# SCH_axp173_3a3036_2022-11-21.net
KiCad netlist of a schematic drawn in EasyEDA
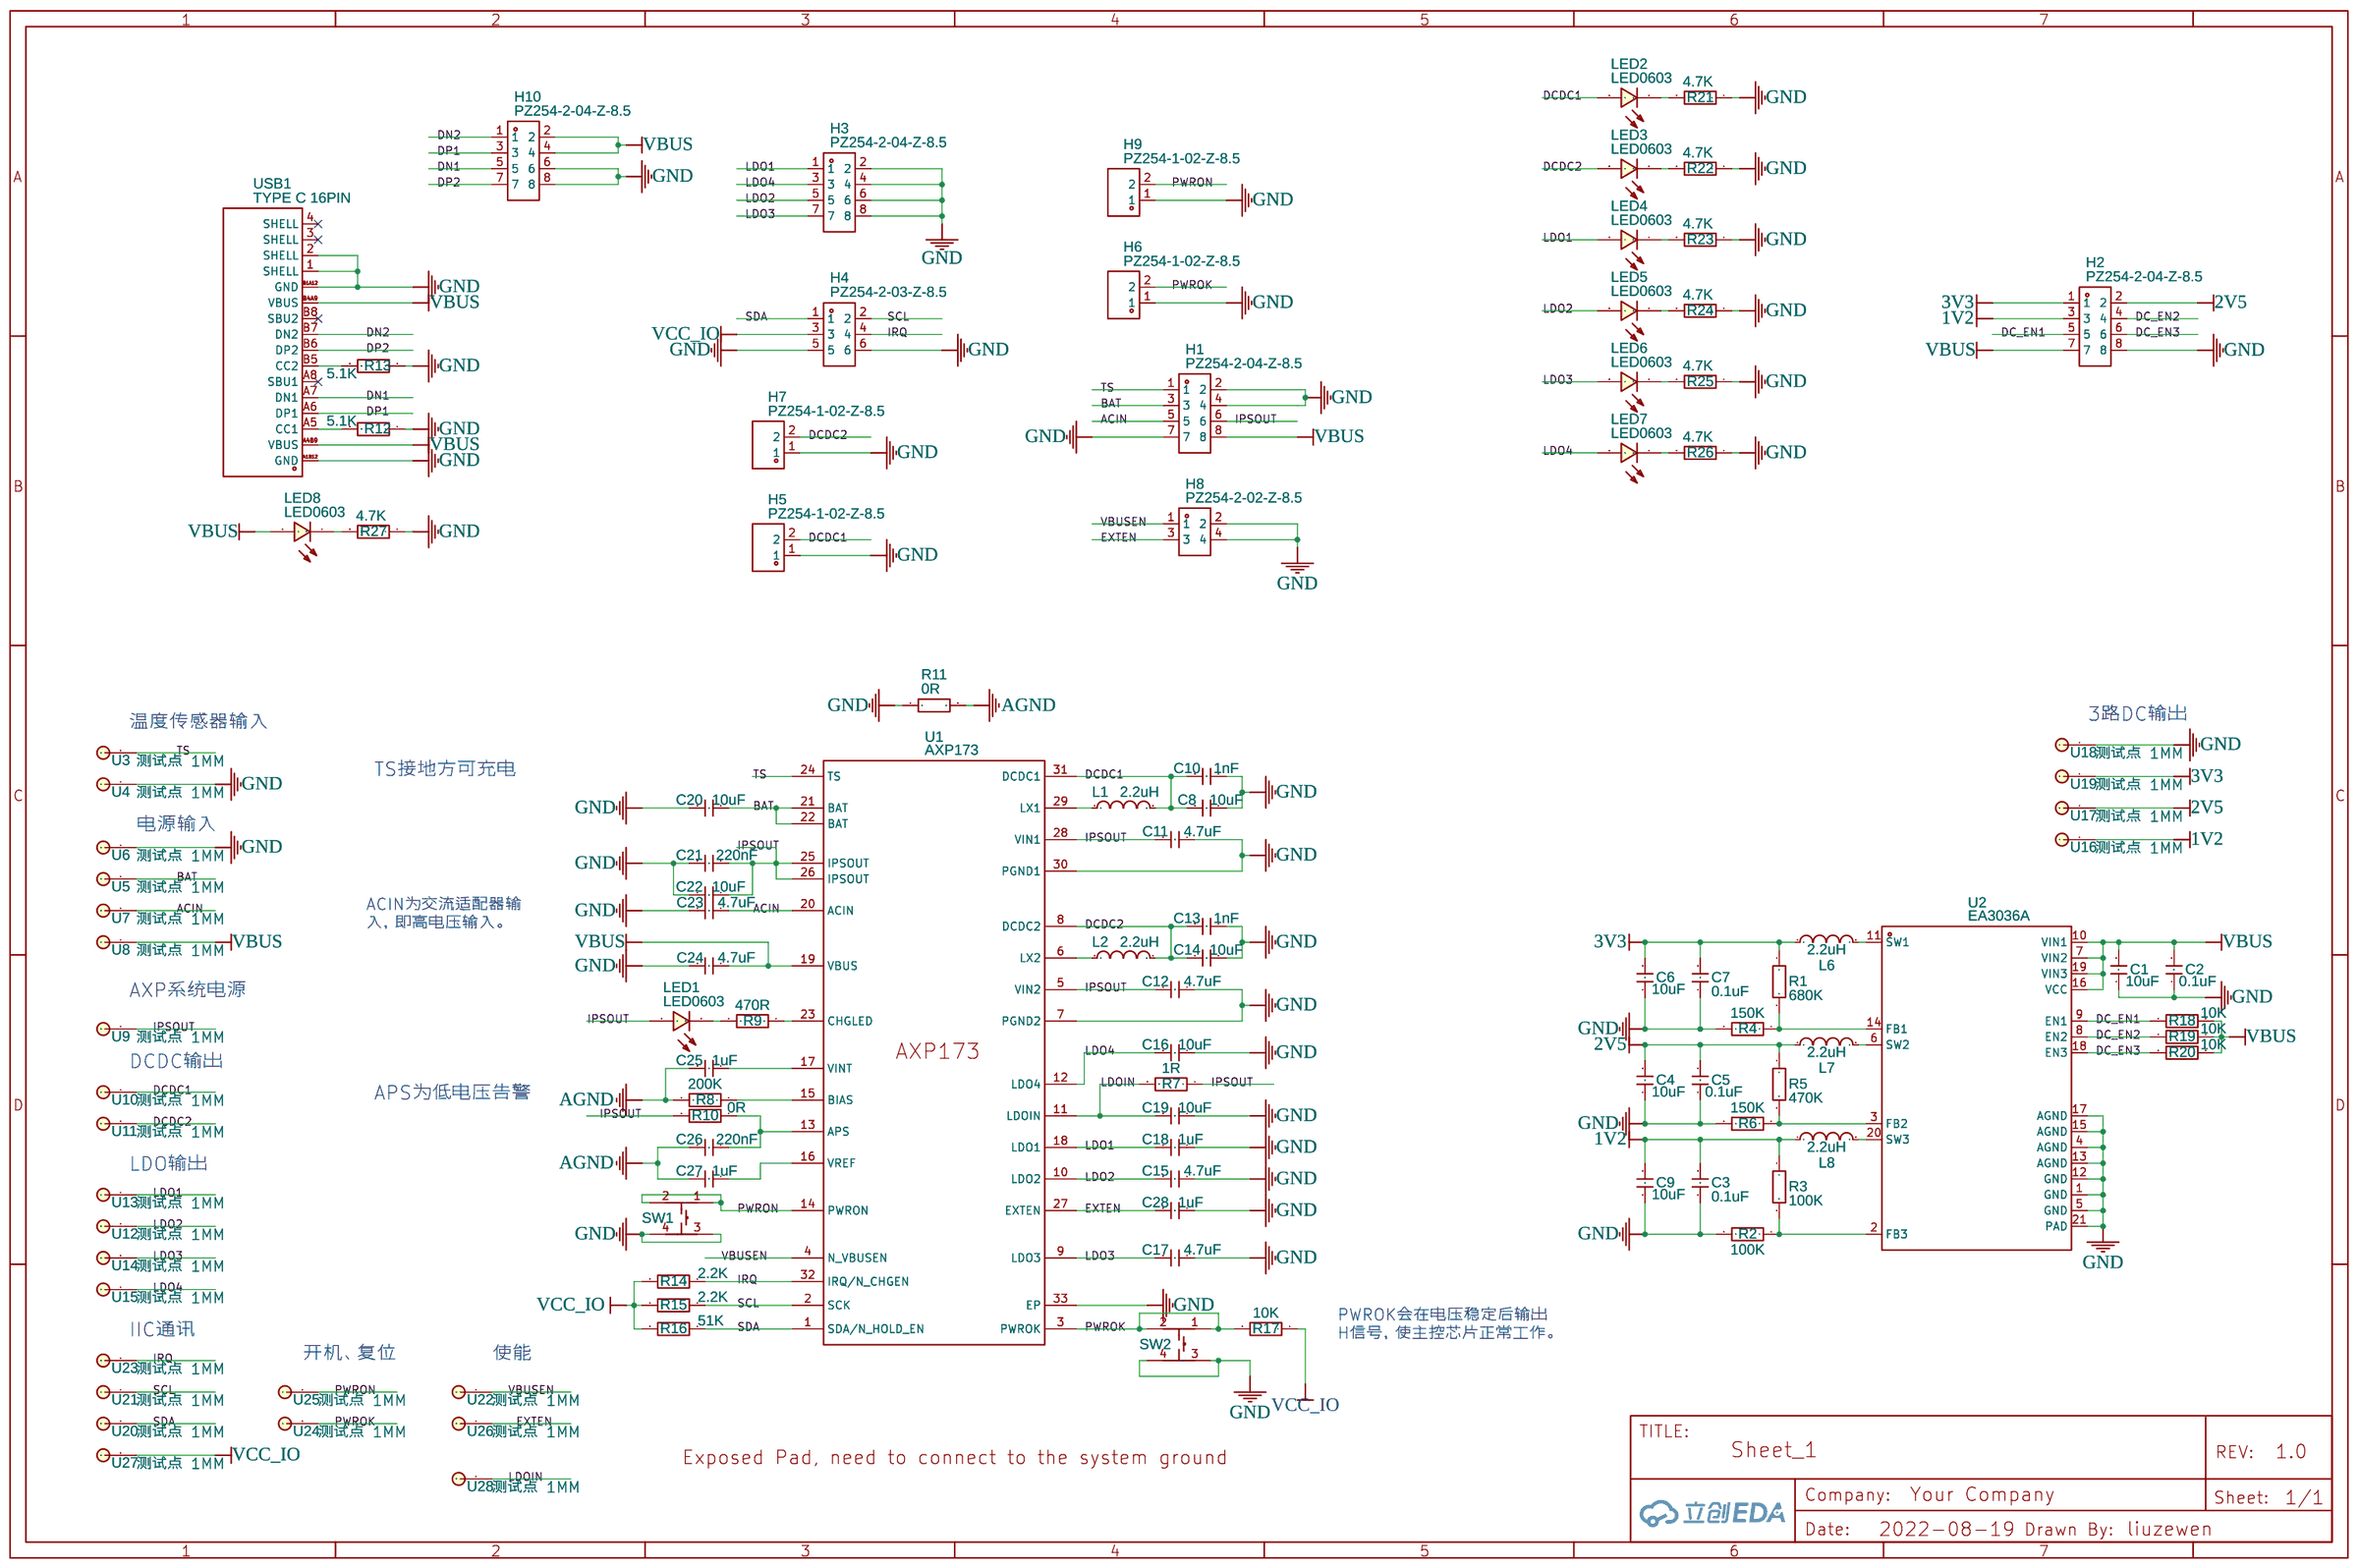
[diagram p0: schematic sheet]

(export (version "E")
  (design (tool "Eeschema 10.0.6"))
  (components
    (comp (ref "C1") (value "10uF") (libsource (lib "") (part "C0603_1")))
    (comp (ref "C2") (value "0.1uF") (libsource (lib "") (part "C0603_1")))
    (comp (ref "C3") (value "0.1uF") (libsource (lib "") (part "C0603_1")))
    (comp (ref "C4") (value "10uF") (libsource (lib "") (part "C0603_1")))
    (comp (ref "C5") (value "0.1uF") (libsource (lib "") (part "C0603_1")))
    (comp (ref "C6") (value "10uF") (libsource (lib "") (part "C0603_1")))
    (comp (ref "C7") (value "0.1uF") (libsource (lib "") (part "C0603_1")))
    (comp (ref "C8") (value "10uF") (libsource (lib "") (part "C0603")))
    (comp (ref "C9") (value "10uF") (libsource (lib "") (part "C0603_1")))
    (comp (ref "C10") (value "1nF") (libsource (lib "") (part "C0603")))
    (comp (ref "C11") (value "4.7uF") (libsource (lib "") (part "C0603")))
    (comp (ref "C12") (value "4.7uF") (libsource (lib "") (part "C0603")))
    (comp (ref "C13") (value "1nF") (libsource (lib "") (part "C0603")))
    (comp (ref "C14") (value "10uF") (libsource (lib "") (part "C0603")))
    (comp (ref "C15") (value "4.7uF") (libsource (lib "") (part "C0603")))
    (comp (ref "C16") (value "10uF") (libsource (lib "") (part "C0603")))
    (comp (ref "C17") (value "4.7uF") (libsource (lib "") (part "C0603")))
    (comp (ref "C18") (value "1uF") (libsource (lib "") (part "C0603")))
    (comp (ref "C19") (value "10uF") (libsource (lib "") (part "C0603")))
    (comp (ref "C20") (value "10uF") (libsource (lib "") (part "C0603")))
    (comp (ref "C21") (value "220nF") (libsource (lib "") (part "C0603")))
    (comp (ref "C22") (value "10uF") (libsource (lib "") (part "C0603")))
    (comp (ref "C23") (value "4.7uF") (libsource (lib "") (part "C0603")))
    (comp (ref "C24") (value "4.7uF") (libsource (lib "") (part "C0603")))
    (comp (ref "C25") (value "1uF") (libsource (lib "") (part "C0603")))
    (comp (ref "C26") (value "220nF") (libsource (lib "") (part "C0603")))
    (comp (ref "C27") (value "1uF") (libsource (lib "") (part "C0603")))
    (comp (ref "C28") (value "1uF") (libsource (lib "") (part "C0603")))
    (comp (ref "H1")
      (value "PZ254-2-04-Z-8.5")
      (fields (field (name "BOM_Supplier Part") "C2894965"))
      (libsource (lib "") (part "PZ254-2-04-Z-8.5"))
    )
    (comp (ref "H2")
      (value "PZ254-2-04-Z-8.5")
      (fields (field (name "BOM_Supplier Part") "C2894965"))
      (libsource (lib "") (part "PZ254-2-04-Z-8.5"))
    )
    (comp (ref "H3")
      (value "PZ254-2-04-Z-8.5")
      (fields (field (name "BOM_Supplier Part") "C2894965"))
      (libsource (lib "") (part "PZ254-2-04-Z-8.5"))
    )
    (comp (ref "H4")
      (value "PZ254-2-03-Z-8.5")
      (fields (field (name "BOM_Supplier Part") "C2894964"))
      (libsource (lib "") (part "PZ254-2-03-Z-8.5"))
    )
    (comp (ref "H5")
      (value "PZ254-1-02-Z-8.5")
      (fields (field (name "BOM_Supplier Part") "C2894925"))
      (libsource (lib "") (part "PZ254-1-02-Z-8.5"))
    )
    (comp (ref "H6")
      (value "PZ254-1-02-Z-8.5")
      (fields (field (name "BOM_Supplier Part") "C2894925"))
      (libsource (lib "") (part "PZ254-1-02-Z-8.5"))
    )
    (comp (ref "H7")
      (value "PZ254-1-02-Z-8.5")
      (fields (field (name "BOM_Supplier Part") "C2894925"))
      (libsource (lib "") (part "PZ254-1-02-Z-8.5"))
    )
    (comp (ref "H8")
      (value "PZ254-2-02-Z-8.5")
      (fields (field (name "BOM_Supplier Part") "C2894963"))
      (libsource (lib "") (part "PZ254-2-02-Z-8.5"))
    )
    (comp (ref "H9")
      (value "PZ254-1-02-Z-8.5")
      (fields (field (name "BOM_Supplier Part") "C2894925"))
      (libsource (lib "") (part "PZ254-1-02-Z-8.5"))
    )
    (comp (ref "H10")
      (value "PZ254-2-04-Z-8.5")
      (fields (field (name "BOM_Supplier Part") "C2894965"))
      (libsource (lib "") (part "PZ254-2-04-Z-8.5"))
    )
    (comp (ref "L1")
      (value "2.2uH")
      (fields
        (field (name "BOM_Manufacturer Part") "FNR252010S2R2NT")
        (field (name "BOM_Supplier Part") "C167682")
      )
      (libsource (lib "") (part "FNR252010S2R2NT"))
    )
    (comp (ref "L2")
      (value "2.2uH")
      (fields
        (field (name "BOM_Manufacturer Part") "FNR252010S2R2NT")
        (field (name "BOM_Supplier Part") "C167682")
      )
      (libsource (lib "") (part "FNR252010S2R2NT"))
    )
    (comp (ref "L6")
      (value "2.2uH")
      (fields
        (field (name "BOM_Manufacturer Part") "CKCS201610-2.2uH/M-N")
        (field (name "BOM_Supplier Part") "C354533")
      )
      (libsource (lib "") (part "CKCS201610-2.2UH/M-N"))
    )
    (comp (ref "L7")
      (value "2.2uH")
      (fields
        (field (name "BOM_Manufacturer Part") "CKCS201610-2.2uH/M-N")
        (field (name "BOM_Supplier Part") "C354533")
      )
      (libsource (lib "") (part "CKCS201610-2.2UH/M-N"))
    )
    (comp (ref "L8")
      (value "2.2uH")
      (fields
        (field (name "BOM_Manufacturer Part") "CKCS201610-2.2uH/M-N")
        (field (name "BOM_Supplier Part") "C354533")
      )
      (libsource (lib "") (part "CKCS201610-2.2UH/M-N"))
    )
    (comp (ref "LED1") (value "LED0603") (libsource (lib "") (part "LED0603")))
    (comp (ref "LED2") (value "LED0603") (libsource (lib "") (part "LED0603")))
    (comp (ref "LED3") (value "LED0603") (libsource (lib "") (part "LED0603")))
    (comp (ref "LED4") (value "LED0603") (libsource (lib "") (part "LED0603")))
    (comp (ref "LED5") (value "LED0603") (libsource (lib "") (part "LED0603")))
    (comp (ref "LED6") (value "LED0603") (libsource (lib "") (part "LED0603")))
    (comp (ref "LED7") (value "LED0603") (libsource (lib "") (part "LED0603")))
    (comp (ref "LED8") (value "LED0603") (libsource (lib "") (part "LED0603")))
    (comp (ref "R1") (value "680K") (libsource (lib "") (part "R0603")))
    (comp (ref "R2") (value "100K") (libsource (lib "") (part "R0603_1")))
    (comp (ref "R3") (value "100K") (libsource (lib "") (part "R0603")))
    (comp (ref "R4") (value "150K") (libsource (lib "") (part "R0603_1")))
    (comp (ref "R5") (value "470K") (libsource (lib "") (part "R0603")))
    (comp (ref "R6") (value "150K") (libsource (lib "") (part "R0603_1")))
    (comp (ref "R7") (value "1R") (libsource (lib "") (part "R0603_1")))
    (comp (ref "R8") (value "200K") (libsource (lib "") (part "R0603_1")))
    (comp (ref "R9") (value "470R") (libsource (lib "") (part "R0603_1")))
    (comp (ref "R10") (value "0R") (libsource (lib "") (part "R0603_1")))
    (comp (ref "R11") (value "0R") (libsource (lib "") (part "R0603_2")))
    (comp (ref "R12") (value "5.1K") (libsource (lib "") (part "R0603_1")))
    (comp (ref "R13") (value "5.1K") (libsource (lib "") (part "R0603_1")))
    (comp (ref "R14") (value "2.2K") (libsource (lib "") (part "R0603_1")))
    (comp (ref "R15") (value "2.2K") (libsource (lib "") (part "R0603_1")))
    (comp (ref "R16") (value "51K") (libsource (lib "") (part "R0603_1")))
    (comp (ref "R17") (value "10K") (libsource (lib "") (part "R0603_1")))
    (comp (ref "R18") (value "10K") (libsource (lib "") (part "R0603_1")))
    (comp (ref "R19") (value "10K") (libsource (lib "") (part "R0603_1")))
    (comp (ref "R20") (value "10K") (libsource (lib "") (part "R0603_1")))
    (comp (ref "R21") (value "4.7K") (libsource (lib "") (part "R0603_1")))
    (comp (ref "R22") (value "4.7K") (libsource (lib "") (part "R0603_1")))
    (comp (ref "R23") (value "4.7K") (libsource (lib "") (part "R0603_1")))
    (comp (ref "R24") (value "4.7K") (libsource (lib "") (part "R0603_1")))
    (comp (ref "R25") (value "4.7K") (libsource (lib "") (part "R0603_1")))
    (comp (ref "R26") (value "4.7K") (libsource (lib "") (part "R0603_1")))
    (comp (ref "R27") (value "4.7K") (libsource (lib "") (part "R0603_1")))
    (comp (ref "SW1")
      (value "UK-B0267-SP25Y")
      (fields (field (name "BOM_Supplier Part") "C493283"))
      (libsource (lib "") (part "UK-B0267-SP25Y"))
    )
    (comp (ref "SW2")
      (value "UK-B0267-SP25Y")
      (fields (field (name "BOM_Supplier Part") "C493283"))
      (libsource (lib "") (part "UK-B0267-SP25Y"))
    )
    (comp (ref "U1")
      (value "AXP173")
      (fields (field (name "BOM_Manufacturer Part") "AXP209"))
      (libsource (lib "") (part "AXP173"))
    )
    (comp (ref "U2") (value "EA3036A") (libsource (lib "") (part "EA3036A")))
    (comp (ref "U3") (value "测试点 1MM") (libsource (lib "") (part "测试点 1MM")))
    (comp (ref "U4") (value "测试点 1MM") (libsource (lib "") (part "测试点 1MM")))
    (comp (ref "U5") (value "测试点 1MM") (libsource (lib "") (part "测试点 1MM")))
    (comp (ref "U6") (value "测试点 1MM") (libsource (lib "") (part "测试点 1MM")))
    (comp (ref "U7") (value "测试点 1MM") (libsource (lib "") (part "测试点 1MM")))
    (comp (ref "U8") (value "测试点 1MM") (libsource (lib "") (part "测试点 1MM")))
    (comp (ref "U9") (value "测试点 1MM") (libsource (lib "") (part "测试点 1MM")))
    (comp (ref "U10") (value "测试点 1MM") (libsource (lib "") (part "测试点 1MM")))
    (comp (ref "U11") (value "测试点 1MM") (libsource (lib "") (part "测试点 1MM")))
    (comp (ref "U12") (value "测试点 1MM") (libsource (lib "") (part "测试点 1MM")))
    (comp (ref "U13") (value "测试点 1MM") (libsource (lib "") (part "测试点 1MM")))
    (comp (ref "U14") (value "测试点 1MM") (libsource (lib "") (part "测试点 1MM")))
    (comp (ref "U15") (value "测试点 1MM") (libsource (lib "") (part "测试点 1MM")))
    (comp (ref "U16") (value "测试点 1MM") (libsource (lib "") (part "测试点 1MM")))
    (comp (ref "U17") (value "测试点 1MM") (libsource (lib "") (part "测试点 1MM")))
    (comp (ref "U18") (value "测试点 1MM") (libsource (lib "") (part "测试点 1MM")))
    (comp (ref "U19") (value "测试点 1MM") (libsource (lib "") (part "测试点 1MM")))
    (comp (ref "U20") (value "测试点 1MM") (libsource (lib "") (part "测试点 1MM")))
    (comp (ref "U21") (value "测试点 1MM") (libsource (lib "") (part "测试点 1MM")))
    (comp (ref "U22") (value "测试点 1MM") (libsource (lib "") (part "测试点 1MM")))
    (comp (ref "U23") (value "测试点 1MM") (libsource (lib "") (part "测试点 1MM")))
    (comp (ref "U24") (value "测试点 1MM") (libsource (lib "") (part "测试点 1MM")))
    (comp (ref "U25") (value "测试点 1MM") (libsource (lib "") (part "测试点 1MM")))
    (comp (ref "U26") (value "测试点 1MM") (libsource (lib "") (part "测试点 1MM")))
    (comp (ref "U27") (value "测试点 1MM") (libsource (lib "") (part "测试点 1MM")))
    (comp (ref "U28") (value "测试点 1MM") (libsource (lib "") (part "测试点 1MM")))
    (comp (ref "USB1")
      (value "TYPE C 16PIN")
      (fields
        (field (name "BOM_Manufacturer Part") "TYPE-C16PIN")
        (field (name "BOM_Supplier Part") "C393939")
      )
      (libsource (lib "") (part "TYPE C 16PIN"))
    )
  )
  (nets
    (net (code "1") (name "/ACIN") (class "Default")
      (node (ref "C23") (pin "1") (pinfunction "1_1") (pintype "unspecified"))
      (node (ref "H1") (pin "5") (pinfunction "5_5") (pintype "unspecified"))
      (node (ref "U1") (pin "20") (pinfunction "ACIN_20") (pintype "unspecified"))
      (node (ref "U7") (pin "1") (pinfunction "1_1") (pintype "unspecified"))
    )
    (net (code "2") (name "/BAT") (class "Default")
      (node (ref "C20") (pin "1") (pinfunction "1_1") (pintype "unspecified"))
      (node (ref "H1") (pin "3") (pinfunction "3_3") (pintype "unspecified"))
      (node (ref "U1") (pin "21") (pinfunction "BAT_21") (pintype "unspecified"))
      (node (ref "U1") (pin "22") (pinfunction "BAT_22") (pintype "unspecified"))
      (node (ref "U5") (pin "1") (pinfunction "1_1") (pintype "unspecified"))
    )
    (net (code "3") (name "/DCDC1") (class "Default")
      (node (ref "C10") (pin "2") (pinfunction "2_2") (pintype "unspecified"))
      (node (ref "C8") (pin "2") (pinfunction "2_2") (pintype "unspecified"))
      (node (ref "H5") (pin "2") (pinfunction "2_2") (pintype "unspecified"))
      (node (ref "L1") (pin "2") (pinfunction "2_2") (pintype "unspecified"))
      (node (ref "LED2") (pin "2") (pinfunction "A_2") (pintype "input"))
      (node (ref "U1") (pin "31") (pinfunction "DCDC1_31") (pintype "unspecified"))
      (node (ref "U10") (pin "1") (pinfunction "1_1") (pintype "unspecified"))
    )
    (net (code "4") (name "/DCDC2") (class "Default")
      (node (ref "C13") (pin "2") (pinfunction "2_2") (pintype "unspecified"))
      (node (ref "C14") (pin "2") (pinfunction "2_2") (pintype "unspecified"))
      (node (ref "H7") (pin "2") (pinfunction "2_2") (pintype "unspecified"))
      (node (ref "L2") (pin "2") (pinfunction "2_2") (pintype "unspecified"))
      (node (ref "LED3") (pin "2") (pinfunction "A_2") (pintype "input"))
      (node (ref "U1") (pin "8") (pinfunction "DCDC2_8") (pintype "unspecified"))
      (node (ref "U11") (pin "1") (pinfunction "1_1") (pintype "unspecified"))
    )
    (net (code "5") (name "/DC_EN1") (class "Default")
      (node (ref "H2") (pin "5") (pinfunction "5_5") (pintype "unspecified"))
      (node (ref "R18") (pin "2") (pinfunction "2_2") (pintype "input"))
      (node (ref "U2") (pin "9") (pinfunction "EN1_9") (pintype "unspecified"))
    )
    (net (code "6") (name "/DC_EN2") (class "Default")
      (node (ref "H2") (pin "4") (pinfunction "4_4") (pintype "unspecified"))
      (node (ref "R19") (pin "2") (pinfunction "2_2") (pintype "input"))
      (node (ref "U2") (pin "8") (pinfunction "EN2_8") (pintype "unspecified"))
    )
    (net (code "7") (name "/DC_EN3") (class "Default")
      (node (ref "H2") (pin "6") (pinfunction "6_6") (pintype "unspecified"))
      (node (ref "R20") (pin "2") (pinfunction "2_2") (pintype "input"))
      (node (ref "U2") (pin "18") (pinfunction "EN3_18") (pintype "unspecified"))
    )
    (net (code "8") (name "/DN1") (class "Default")
      (node (ref "H10") (pin "5") (pinfunction "5_5") (pintype "unspecified"))
      (node (ref "USB1") (pin "A7") (pinfunction "DN1_A7") (pintype "unspecified"))
    )
    (net (code "9") (name "/DN2") (class "Default")
      (node (ref "H10") (pin "1") (pinfunction "1_1") (pintype "unspecified"))
      (node (ref "USB1") (pin "B7") (pinfunction "DN2_B7") (pintype "unspecified"))
    )
    (net (code "10") (name "/DP1") (class "Default")
      (node (ref "H10") (pin "3") (pinfunction "3_3") (pintype "unspecified"))
      (node (ref "USB1") (pin "A6") (pinfunction "DP1_A6") (pintype "unspecified"))
    )
    (net (code "11") (name "/DP2") (class "Default")
      (node (ref "H10") (pin "7") (pinfunction "7_7") (pintype "unspecified"))
      (node (ref "USB1") (pin "B6") (pinfunction "DP2_B6") (pintype "unspecified"))
    )
    (net (code "12") (name "/EXTEN") (class "Default")
      (node (ref "C28") (pin "2") (pinfunction "2_2") (pintype "unspecified"))
      (node (ref "H8") (pin "3") (pinfunction "3_3") (pintype "unspecified"))
      (node (ref "U1") (pin "27") (pinfunction "EXTEN_27") (pintype "unspecified"))
      (node (ref "U26") (pin "1") (pinfunction "1_1") (pintype "unspecified"))
    )
    (net (code "13") (name "/IPSOUT") (class "Default")
      (node (ref "C11") (pin "2") (pinfunction "2_2") (pintype "unspecified"))
      (node (ref "C12") (pin "2") (pinfunction "2_2") (pintype "unspecified"))
      (node (ref "C21") (pin "1") (pinfunction "1_1") (pintype "unspecified"))
      (node (ref "C22") (pin "1") (pinfunction "1_1") (pintype "unspecified"))
      (node (ref "H1") (pin "6") (pinfunction "6_6") (pintype "unspecified"))
      (node (ref "LED1") (pin "2") (pinfunction "A_2") (pintype "input"))
      (node (ref "R10") (pin "2") (pinfunction "2_2") (pintype "input"))
      (node (ref "R7") (pin "1") (pinfunction "1_1") (pintype "input"))
      (node (ref "U1") (pin "25") (pinfunction "IPSOUT_25") (pintype "unspecified"))
      (node (ref "U1") (pin "26") (pinfunction "IPSOUT_26") (pintype "unspecified"))
      (node (ref "U1") (pin "28") (pinfunction "VIN1_28") (pintype "unspecified"))
      (node (ref "U1") (pin "5") (pinfunction "VIN2_5") (pintype "unspecified"))
      (node (ref "U9") (pin "1") (pinfunction "1_1") (pintype "unspecified"))
    )
    (net (code "14") (name "/IRQ") (class "Default")
      (node (ref "H4") (pin "4") (pinfunction "4_4") (pintype "unspecified"))
      (node (ref "R14") (pin "1") (pinfunction "1_1") (pintype "input"))
      (node (ref "U1") (pin "32") (pinfunction "IRQ/N_CHGEN_32") (pintype "unspecified"))
      (node (ref "U23") (pin "1") (pinfunction "1_1") (pintype "unspecified"))
    )
    (net (code "15") (name "/LDO1") (class "Default")
      (node (ref "C18") (pin "2") (pinfunction "2_2") (pintype "unspecified"))
      (node (ref "H3") (pin "1") (pinfunction "1_1") (pintype "unspecified"))
      (node (ref "LED4") (pin "2") (pinfunction "A_2") (pintype "input"))
      (node (ref "U1") (pin "18") (pinfunction "LDO1_18") (pintype "unspecified"))
      (node (ref "U13") (pin "1") (pinfunction "1_1") (pintype "unspecified"))
    )
    (net (code "16") (name "/LDO2") (class "Default")
      (node (ref "C15") (pin "2") (pinfunction "2_2") (pintype "unspecified"))
      (node (ref "H3") (pin "5") (pinfunction "5_5") (pintype "unspecified"))
      (node (ref "LED5") (pin "2") (pinfunction "A_2") (pintype "input"))
      (node (ref "U1") (pin "10") (pinfunction "LDO2_10") (pintype "unspecified"))
      (node (ref "U12") (pin "1") (pinfunction "1_1") (pintype "unspecified"))
    )
    (net (code "17") (name "/LDO3") (class "Default")
      (node (ref "C17") (pin "2") (pinfunction "2_2") (pintype "unspecified"))
      (node (ref "H3") (pin "7") (pinfunction "7_7") (pintype "unspecified"))
      (node (ref "LED6") (pin "2") (pinfunction "A_2") (pintype "input"))
      (node (ref "U1") (pin "9") (pinfunction "LDO3_9") (pintype "unspecified"))
      (node (ref "U14") (pin "1") (pinfunction "1_1") (pintype "unspecified"))
    )
    (net (code "18") (name "/LDO4") (class "Default")
      (node (ref "C16") (pin "2") (pinfunction "2_2") (pintype "unspecified"))
      (node (ref "H3") (pin "3") (pinfunction "3_3") (pintype "unspecified"))
      (node (ref "LED7") (pin "2") (pinfunction "A_2") (pintype "input"))
      (node (ref "U1") (pin "12") (pinfunction "LDO4_12") (pintype "unspecified"))
      (node (ref "U15") (pin "1") (pinfunction "1_1") (pintype "unspecified"))
    )
    (net (code "19") (name "/LDOIN") (class "Default")
      (node (ref "C19") (pin "2") (pinfunction "2_2") (pintype "unspecified"))
      (node (ref "R7") (pin "2") (pinfunction "2_2") (pintype "input"))
      (node (ref "U1") (pin "11") (pinfunction "LDOIN_11") (pintype "unspecified"))
      (node (ref "U28") (pin "1") (pinfunction "1_1") (pintype "unspecified"))
    )
    (net (code "20") (name "/PWROK") (class "Default")
      (node (ref "H6") (pin "2") (pinfunction "2_2") (pintype "unspecified"))
      (node (ref "R17") (pin "2") (pinfunction "2_2") (pintype "input"))
      (node (ref "SW2") (pin "1") (pinfunction "1_1") (pintype "unspecified"))
      (node (ref "SW2") (pin "2") (pinfunction "2_2") (pintype "unspecified"))
      (node (ref "U1") (pin "3") (pinfunction "PWROK_3") (pintype "unspecified"))
      (node (ref "U24") (pin "1") (pinfunction "1_1") (pintype "unspecified"))
    )
    (net (code "21") (name "/PWRON") (class "Default")
      (node (ref "H9") (pin "2") (pinfunction "2_2") (pintype "unspecified"))
      (node (ref "SW1") (pin "1") (pinfunction "1_1") (pintype "unspecified"))
      (node (ref "SW1") (pin "2") (pinfunction "2_2") (pintype "unspecified"))
      (node (ref "U1") (pin "14") (pinfunction "PWRON_14") (pintype "unspecified"))
      (node (ref "U25") (pin "1") (pinfunction "1_1") (pintype "unspecified"))
    )
    (net (code "22") (name "/SCL") (class "Default")
      (node (ref "H4") (pin "2") (pinfunction "2_2") (pintype "unspecified"))
      (node (ref "R15") (pin "1") (pinfunction "1_1") (pintype "input"))
      (node (ref "U1") (pin "2") (pinfunction "SCK_2") (pintype "unspecified"))
      (node (ref "U21") (pin "1") (pinfunction "1_1") (pintype "unspecified"))
    )
    (net (code "23") (name "/SDA") (class "Default")
      (node (ref "H4") (pin "1") (pinfunction "1_1") (pintype "unspecified"))
      (node (ref "R16") (pin "1") (pinfunction "1_1") (pintype "input"))
      (node (ref "U1") (pin "1") (pinfunction "SDA/N_HOLD_EN_1") (pintype "unspecified"))
      (node (ref "U20") (pin "1") (pinfunction "1_1") (pintype "unspecified"))
    )
    (net (code "24") (name "/TS") (class "Default")
      (node (ref "H1") (pin "1") (pinfunction "1_1") (pintype "unspecified"))
      (node (ref "U1") (pin "24") (pinfunction "TS_24") (pintype "unspecified"))
      (node (ref "U3") (pin "1") (pinfunction "1_1") (pintype "unspecified"))
    )
    (net (code "25") (name "/VBUSEN") (class "Default")
      (node (ref "H8") (pin "1") (pinfunction "1_1") (pintype "unspecified"))
      (node (ref "U1") (pin "4") (pinfunction "N_VBUSEN_4") (pintype "unspecified"))
      (node (ref "U22") (pin "1") (pinfunction "1_1") (pintype "unspecified"))
    )
    (net (code "26") (name "1V2") (class "Default")
      (node (ref "C3") (pin "2") (pinfunction "2_2") (pintype "unspecified"))
      (node (ref "C9") (pin "2") (pinfunction "2_2") (pintype "unspecified"))
      (node (ref "H2") (pin "3") (pinfunction "3_3") (pintype "unspecified"))
      (node (ref "L8") (pin "1") (pinfunction "1_1") (pintype "unspecified"))
      (node (ref "R3") (pin "1") (pinfunction "1_1") (pintype "input"))
      (node (ref "U16") (pin "1") (pinfunction "1_1") (pintype "unspecified"))
    )
    (net (code "27") (name "2V5") (class "Default")
      (node (ref "C4") (pin "2") (pinfunction "2_2") (pintype "unspecified"))
      (node (ref "C5") (pin "2") (pinfunction "2_2") (pintype "unspecified"))
      (node (ref "H2") (pin "2") (pinfunction "2_2") (pintype "unspecified"))
      (node (ref "L7") (pin "1") (pinfunction "1_1") (pintype "unspecified"))
      (node (ref "R5") (pin "1") (pinfunction "1_1") (pintype "input"))
      (node (ref "U17") (pin "1") (pinfunction "1_1") (pintype "unspecified"))
    )
    (net (code "28") (name "3V3") (class "Default")
      (node (ref "C6") (pin "2") (pinfunction "2_2") (pintype "unspecified"))
      (node (ref "C7") (pin "2") (pinfunction "2_2") (pintype "unspecified"))
      (node (ref "H2") (pin "1") (pinfunction "1_1") (pintype "unspecified"))
      (node (ref "L6") (pin "1") (pinfunction "1_1") (pintype "unspecified"))
      (node (ref "R1") (pin "1") (pinfunction "1_1") (pintype "input"))
      (node (ref "U19") (pin "1") (pinfunction "1_1") (pintype "unspecified"))
    )
    (net (code "29") (name "AGND") (class "Default")
      (node (ref "C25") (pin "2") (pinfunction "2_2") (pintype "unspecified"))
      (node (ref "C26") (pin "2") (pinfunction "2_2") (pintype "unspecified"))
      (node (ref "C27") (pin "2") (pinfunction "2_2") (pintype "unspecified"))
      (node (ref "R11") (pin "2") (pinfunction "2_2") (pintype "input"))
      (node (ref "R8") (pin "2") (pinfunction "2_2") (pintype "input"))
    )
    (net (code "30") (name "GND") (class "Default")
      (node (ref "C1") (pin "1") (pinfunction "1_1") (pintype "unspecified"))
      (node (ref "C10") (pin "1") (pinfunction "1_1") (pintype "unspecified"))
      (node (ref "C11") (pin "1") (pinfunction "1_1") (pintype "unspecified"))
      (node (ref "C12") (pin "1") (pinfunction "1_1") (pintype "unspecified"))
      (node (ref "C13") (pin "1") (pinfunction "1_1") (pintype "unspecified"))
      (node (ref "C14") (pin "1") (pinfunction "1_1") (pintype "unspecified"))
      (node (ref "C15") (pin "1") (pinfunction "1_1") (pintype "unspecified"))
      (node (ref "C16") (pin "1") (pinfunction "1_1") (pintype "unspecified"))
      (node (ref "C17") (pin "1") (pinfunction "1_1") (pintype "unspecified"))
      (node (ref "C18") (pin "1") (pinfunction "1_1") (pintype "unspecified"))
      (node (ref "C19") (pin "1") (pinfunction "1_1") (pintype "unspecified"))
      (node (ref "C2") (pin "1") (pinfunction "1_1") (pintype "unspecified"))
      (node (ref "C20") (pin "2") (pinfunction "2_2") (pintype "unspecified"))
      (node (ref "C21") (pin "2") (pinfunction "2_2") (pintype "unspecified"))
      (node (ref "C22") (pin "2") (pinfunction "2_2") (pintype "unspecified"))
      (node (ref "C23") (pin "2") (pinfunction "2_2") (pintype "unspecified"))
      (node (ref "C24") (pin "2") (pinfunction "2_2") (pintype "unspecified"))
      (node (ref "C28") (pin "1") (pinfunction "1_1") (pintype "unspecified"))
      (node (ref "C3") (pin "1") (pinfunction "1_1") (pintype "unspecified"))
      (node (ref "C4") (pin "1") (pinfunction "1_1") (pintype "unspecified"))
      (node (ref "C5") (pin "1") (pinfunction "1_1") (pintype "unspecified"))
      (node (ref "C6") (pin "1") (pinfunction "1_1") (pintype "unspecified"))
      (node (ref "C7") (pin "1") (pinfunction "1_1") (pintype "unspecified"))
      (node (ref "C8") (pin "1") (pinfunction "1_1") (pintype "unspecified"))
      (node (ref "C9") (pin "1") (pinfunction "1_1") (pintype "unspecified"))
      (node (ref "H1") (pin "2") (pinfunction "2_2") (pintype "unspecified"))
      (node (ref "H1") (pin "4") (pinfunction "4_4") (pintype "unspecified"))
      (node (ref "H1") (pin "7") (pinfunction "7_7") (pintype "unspecified"))
      (node (ref "H10") (pin "6") (pinfunction "6_6") (pintype "unspecified"))
      (node (ref "H10") (pin "8") (pinfunction "8_8") (pintype "unspecified"))
      (node (ref "H2") (pin "8") (pinfunction "8_8") (pintype "unspecified"))
      (node (ref "H3") (pin "2") (pinfunction "2_2") (pintype "unspecified"))
      (node (ref "H3") (pin "4") (pinfunction "4_4") (pintype "unspecified"))
      (node (ref "H3") (pin "6") (pinfunction "6_6") (pintype "unspecified"))
      (node (ref "H3") (pin "8") (pinfunction "8_8") (pintype "unspecified"))
      (node (ref "H4") (pin "5") (pinfunction "5_5") (pintype "unspecified"))
      (node (ref "H4") (pin "6") (pinfunction "6_6") (pintype "unspecified"))
      (node (ref "H5") (pin "1") (pinfunction "1_1") (pintype "unspecified"))
      (node (ref "H6") (pin "1") (pinfunction "1_1") (pintype "unspecified"))
      (node (ref "H7") (pin "1") (pinfunction "1_1") (pintype "unspecified"))
      (node (ref "H8") (pin "2") (pinfunction "2_2") (pintype "unspecified"))
      (node (ref "H8") (pin "4") (pinfunction "4_4") (pintype "unspecified"))
      (node (ref "H9") (pin "1") (pinfunction "1_1") (pintype "unspecified"))
      (node (ref "R11") (pin "1") (pinfunction "1_1") (pintype "input"))
      (node (ref "R12") (pin "1") (pinfunction "1_1") (pintype "input"))
      (node (ref "R13") (pin "1") (pinfunction "1_1") (pintype "input"))
      (node (ref "R2") (pin "2") (pinfunction "2_2") (pintype "input"))
      (node (ref "R21") (pin "1") (pinfunction "1_1") (pintype "input"))
      (node (ref "R22") (pin "1") (pinfunction "1_1") (pintype "input"))
      (node (ref "R23") (pin "1") (pinfunction "1_1") (pintype "input"))
      (node (ref "R24") (pin "1") (pinfunction "1_1") (pintype "input"))
      (node (ref "R25") (pin "1") (pinfunction "1_1") (pintype "input"))
      (node (ref "R26") (pin "1") (pinfunction "1_1") (pintype "input"))
      (node (ref "R27") (pin "1") (pinfunction "1_1") (pintype "input"))
      (node (ref "R4") (pin "2") (pinfunction "2_2") (pintype "input"))
      (node (ref "R6") (pin "2") (pinfunction "2_2") (pintype "input"))
      (node (ref "SW1") (pin "3") (pinfunction "3_3") (pintype "unspecified"))
      (node (ref "SW1") (pin "4") (pinfunction "4_4") (pintype "unspecified"))
      (node (ref "SW2") (pin "3") (pinfunction "3_3") (pintype "unspecified"))
      (node (ref "SW2") (pin "4") (pinfunction "4_4") (pintype "unspecified"))
      (node (ref "U1") (pin "30") (pinfunction "PGND1_30") (pintype "unspecified"))
      (node (ref "U1") (pin "33") (pinfunction "EP_33") (pintype "unspecified"))
      (node (ref "U1") (pin "7") (pinfunction "PGND2_7") (pintype "unspecified"))
      (node (ref "U18") (pin "1") (pinfunction "1_1") (pintype "unspecified"))
      (node (ref "U2") (pin "1") (pinfunction "GND_1") (pintype "unspecified"))
      (node (ref "U2") (pin "12") (pinfunction "GND_12") (pintype "unspecified"))
      (node (ref "U2") (pin "13") (pinfunction "AGND_13") (pintype "unspecified"))
      (node (ref "U2") (pin "15") (pinfunction "AGND_15") (pintype "unspecified"))
      (node (ref "U2") (pin "17") (pinfunction "AGND_17") (pintype "unspecified"))
      (node (ref "U2") (pin "21") (pinfunction "PAD_21") (pintype "unspecified"))
      (node (ref "U2") (pin "4") (pinfunction "AGND_4") (pintype "unspecified"))
      (node (ref "U2") (pin "5") (pinfunction "GND_5") (pintype "unspecified"))
      (node (ref "U4") (pin "1") (pinfunction "1_1") (pintype "unspecified"))
      (node (ref "U6") (pin "1") (pinfunction "1_1") (pintype "unspecified"))
      (node (ref "USB1") (pin "1") (pinfunction "SHELL_1") (pintype "unspecified"))
      (node (ref "USB1") (pin "2") (pinfunction "SHELL_2") (pintype "unspecified"))
      (node (ref "USB1") (pin "A1B12") (pinfunction "GND_A1B12") (pintype "unspecified"))
      (node (ref "USB1") (pin "B1A12") (pinfunction "GND_B1A12") (pintype "unspecified"))
    )
    (net (code "31") (name "Net-(LED1-C)") (class "Default")
      (node (ref "LED1") (pin "1") (pinfunction "C_1") (pintype "input"))
      (node (ref "R9") (pin "2") (pinfunction "2_2") (pintype "input"))
    )
    (net (code "32") (name "Net-(LED2-C)") (class "Default")
      (node (ref "LED2") (pin "1") (pinfunction "C_1") (pintype "input"))
      (node (ref "R21") (pin "2") (pinfunction "2_2") (pintype "input"))
    )
    (net (code "33") (name "Net-(LED3-C)") (class "Default")
      (node (ref "LED3") (pin "1") (pinfunction "C_1") (pintype "input"))
      (node (ref "R22") (pin "2") (pinfunction "2_2") (pintype "input"))
    )
    (net (code "34") (name "Net-(LED4-C)") (class "Default")
      (node (ref "LED4") (pin "1") (pinfunction "C_1") (pintype "input"))
      (node (ref "R23") (pin "2") (pinfunction "2_2") (pintype "input"))
    )
    (net (code "35") (name "Net-(LED5-C)") (class "Default")
      (node (ref "LED5") (pin "1") (pinfunction "C_1") (pintype "input"))
      (node (ref "R24") (pin "2") (pinfunction "2_2") (pintype "input"))
    )
    (net (code "36") (name "Net-(LED6-C)") (class "Default")
      (node (ref "LED6") (pin "1") (pinfunction "C_1") (pintype "input"))
      (node (ref "R25") (pin "2") (pinfunction "2_2") (pintype "input"))
    )
    (net (code "37") (name "Net-(LED7-C)") (class "Default")
      (node (ref "LED7") (pin "1") (pinfunction "C_1") (pintype "input"))
      (node (ref "R26") (pin "2") (pinfunction "2_2") (pintype "input"))
    )
    (net (code "38") (name "Net-(LED8-C)") (class "Default")
      (node (ref "LED8") (pin "1") (pinfunction "C_1") (pintype "input"))
      (node (ref "R27") (pin "2") (pinfunction "2_2") (pintype "input"))
    )
    (net (code "39") (name "Net-(U1-APS)") (class "Default")
      (node (ref "C26") (pin "1") (pinfunction "1_1") (pintype "unspecified"))
      (node (ref "R10") (pin "1") (pinfunction "1_1") (pintype "input"))
      (node (ref "U1") (pin "13") (pinfunction "APS_13") (pintype "unspecified"))
    )
    (net (code "40") (name "Net-(U1-BIAS)") (class "Default")
      (node (ref "R8") (pin "1") (pinfunction "1_1") (pintype "input"))
      (node (ref "U1") (pin "15") (pinfunction "BIAS_15") (pintype "unspecified"))
    )
    (net (code "41") (name "Net-(U1-CHGLED)") (class "Default")
      (node (ref "R9") (pin "1") (pinfunction "1_1") (pintype "input"))
      (node (ref "U1") (pin "23") (pinfunction "CHGLED_23") (pintype "unspecified"))
    )
    (net (code "42") (name "Net-(U1-LX1)") (class "Default")
      (node (ref "L1") (pin "1") (pinfunction "1_1") (pintype "unspecified"))
      (node (ref "U1") (pin "29") (pinfunction "LX1_29") (pintype "unspecified"))
    )
    (net (code "43") (name "Net-(U1-LX2)") (class "Default")
      (node (ref "L2") (pin "1") (pinfunction "1_1") (pintype "unspecified"))
      (node (ref "U1") (pin "6") (pinfunction "LX2_6") (pintype "unspecified"))
    )
    (net (code "44") (name "Net-(U1-VINT)") (class "Default")
      (node (ref "C25") (pin "1") (pinfunction "1_1") (pintype "unspecified"))
      (node (ref "U1") (pin "17") (pinfunction "VINT_17") (pintype "unspecified"))
    )
    (net (code "45") (name "Net-(U1-VREF)") (class "Default")
      (node (ref "C27") (pin "1") (pinfunction "1_1") (pintype "unspecified"))
      (node (ref "U1") (pin "16") (pinfunction "VREF_16") (pintype "unspecified"))
    )
    (net (code "46") (name "Net-(U2-FB1)") (class "Default")
      (node (ref "R1") (pin "2") (pinfunction "2_2") (pintype "input"))
      (node (ref "R4") (pin "1") (pinfunction "1_1") (pintype "input"))
      (node (ref "U2") (pin "14") (pinfunction "FB1_14") (pintype "unspecified"))
    )
    (net (code "47") (name "Net-(U2-FB2)") (class "Default")
      (node (ref "R5") (pin "2") (pinfunction "2_2") (pintype "input"))
      (node (ref "R6") (pin "1") (pinfunction "1_1") (pintype "input"))
      (node (ref "U2") (pin "3") (pinfunction "FB2_3") (pintype "unspecified"))
    )
    (net (code "48") (name "Net-(U2-FB3)") (class "Default")
      (node (ref "R2") (pin "1") (pinfunction "1_1") (pintype "input"))
      (node (ref "R3") (pin "2") (pinfunction "2_2") (pintype "input"))
      (node (ref "U2") (pin "2") (pinfunction "FB3_2") (pintype "unspecified"))
    )
    (net (code "49") (name "Net-(U2-SW1)") (class "Default")
      (node (ref "L6") (pin "2") (pinfunction "2_2") (pintype "unspecified"))
      (node (ref "U2") (pin "11") (pinfunction "SW1_11") (pintype "unspecified"))
    )
    (net (code "50") (name "Net-(U2-SW2)") (class "Default")
      (node (ref "L7") (pin "2") (pinfunction "2_2") (pintype "unspecified"))
      (node (ref "U2") (pin "6") (pinfunction "SW2_6") (pintype "unspecified"))
    )
    (net (code "51") (name "Net-(U2-SW3)") (class "Default")
      (node (ref "L8") (pin "2") (pinfunction "2_2") (pintype "unspecified"))
      (node (ref "U2") (pin "20") (pinfunction "SW3_20") (pintype "unspecified"))
    )
    (net (code "52") (name "Net-(USB1-CC1)") (class "Default")
      (node (ref "R12") (pin "2") (pinfunction "2_2") (pintype "input"))
      (node (ref "USB1") (pin "A5") (pinfunction "CC1_A5") (pintype "unspecified"))
    )
    (net (code "53") (name "Net-(USB1-CC2)") (class "Default")
      (node (ref "R13") (pin "2") (pinfunction "2_2") (pintype "input"))
      (node (ref "USB1") (pin "B5") (pinfunction "CC2_B5") (pintype "unspecified"))
    )
    (net (code "54") (name "VBUS") (class "Default")
      (node (ref "C1") (pin "2") (pinfunction "2_2") (pintype "unspecified"))
      (node (ref "C2") (pin "2") (pinfunction "2_2") (pintype "unspecified"))
      (node (ref "C24") (pin "1") (pinfunction "1_1") (pintype "unspecified"))
      (node (ref "H1") (pin "8") (pinfunction "8_8") (pintype "unspecified"))
      (node (ref "H10") (pin "2") (pinfunction "2_2") (pintype "unspecified"))
      (node (ref "H10") (pin "4") (pinfunction "4_4") (pintype "unspecified"))
      (node (ref "H2") (pin "7") (pinfunction "7_7") (pintype "unspecified"))
      (node (ref "LED8") (pin "2") (pinfunction "A_2") (pintype "input"))
      (node (ref "R18") (pin "1") (pinfunction "1_1") (pintype "input"))
      (node (ref "R19") (pin "1") (pinfunction "1_1") (pintype "input"))
      (node (ref "R20") (pin "1") (pinfunction "1_1") (pintype "input"))
      (node (ref "U1") (pin "19") (pinfunction "VBUS_19") (pintype "unspecified"))
      (node (ref "U2") (pin "10") (pinfunction "VIN1_10") (pintype "unspecified"))
      (node (ref "U2") (pin "16") (pinfunction "VCC_16") (pintype "unspecified"))
      (node (ref "U2") (pin "19") (pinfunction "VIN3_19") (pintype "unspecified"))
      (node (ref "U2") (pin "7") (pinfunction "VIN2_7") (pintype "unspecified"))
      (node (ref "U8") (pin "1") (pinfunction "1_1") (pintype "unspecified"))
      (node (ref "USB1") (pin "A4B9") (pinfunction "VBUS_A4B9") (pintype "unspecified"))
      (node (ref "USB1") (pin "B4A9") (pinfunction "VBUS_B4A9") (pintype "unspecified"))
    )
    (net (code "55") (name "VCC_IO") (class "Default")
      (node (ref "H4") (pin "3") (pinfunction "3_3") (pintype "unspecified"))
      (node (ref "R14") (pin "2") (pinfunction "2_2") (pintype "input"))
      (node (ref "R15") (pin "2") (pinfunction "2_2") (pintype "input"))
      (node (ref "R16") (pin "2") (pinfunction "2_2") (pintype "input"))
      (node (ref "R17") (pin "1") (pinfunction "1_1") (pintype "input"))
      (node (ref "U27") (pin "1") (pinfunction "1_1") (pintype "unspecified"))
    )
    (net (code "56") (name "unconnected-(USB1-SBU1-PadA8)") (class "Default")
      (node (ref "USB1") (pin "A8") (pinfunction "SBU1_A8") (pintype "unspecified+no_connect"))
    )
    (net (code "57") (name "unconnected-(USB1-SBU2-PadB8)") (class "Default")
      (node (ref "USB1") (pin "B8") (pinfunction "SBU2_B8") (pintype "unspecified+no_connect"))
    )
    (net (code "58") (name "unconnected-(USB1-SHELL-Pad3)") (class "Default")
      (node (ref "USB1") (pin "3") (pinfunction "SHELL_3") (pintype "unspecified+no_connect"))
    )
    (net (code "59") (name "unconnected-(USB1-SHELL-Pad4)") (class "Default")
      (node (ref "USB1") (pin "4") (pinfunction "SHELL_4") (pintype "unspecified+no_connect"))
    )
  )
)
